# Cording.net
KiCad netlist of a schematic drawn in Altium Designer
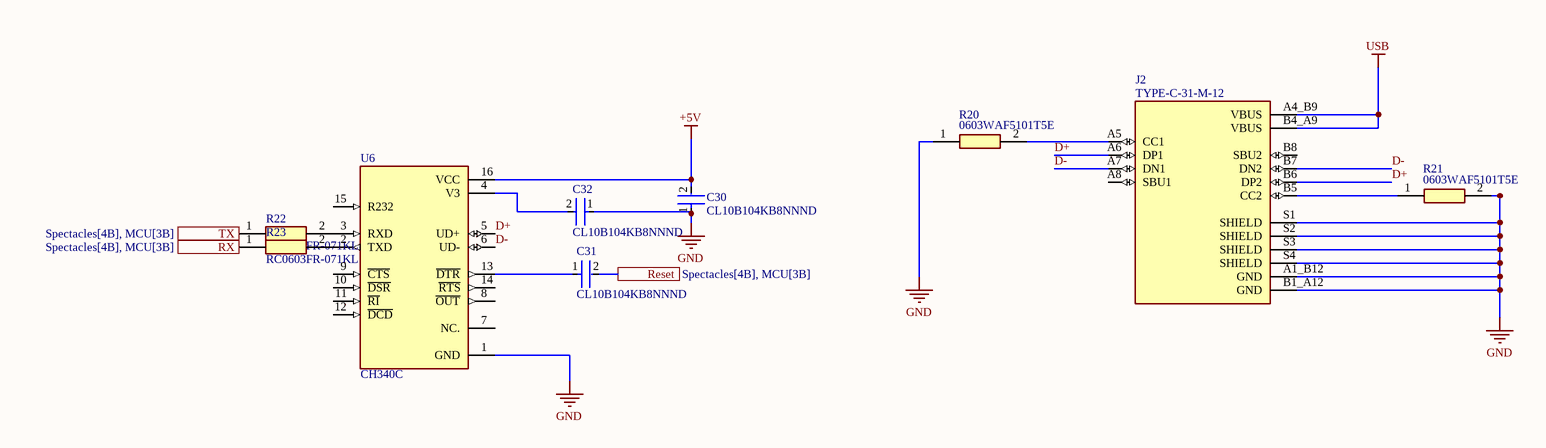
[diagram p0: Cording.SchDoc]

(export (version "E")
  (design (tool "Eeschema 10.0.6"))
  (components
    (comp (ref "C30")
      (value "CL10B104KB8NNND")
      (footprint "FP-CL10-IPC_A")
      (description "Cap Ceramic 100nF 50V X7R ±10% Pad SMD 0603 +125°C T/R")
      (fields (field (name "VOLTAGE") "50V") (field (name "TOLERANCE") "10%"))
      (libsource (lib "Altium Content Vault") (part "b4654b650e69147ec39a6b967a45e02"))
    )
    (comp (ref "C31")
      (value "CL10B104KB8NNND")
      (footprint "FP-CL10-IPC_A")
      (description "Cap Ceramic 100nF 50V X7R ±10% Pad SMD 0603 +125°C T/R")
      (fields (field (name "VOLTAGE") "50V") (field (name "TOLERANCE") "10%"))
      (libsource (lib "Altium Content Vault") (part "b4654b650e69147ec39a6b967a45e02"))
    )
    (comp (ref "C32")
      (value "CL10B104KB8NNND")
      (footprint "FP-CL10-IPC_A")
      (description "Cap Ceramic 100nF 50V X7R ±10% Pad SMD 0603 +125°C T/R")
      (fields (field (name "VOLTAGE") "50V") (field (name "TOLERANCE") "10%"))
      (libsource (lib "Altium Content Vault") (part "b4654b650e69147ec39a6b967a45e02"))
    )
    (comp (ref "J2")
      (value "TYPE-C-31-M-12")
      (footprint "HRO_TYPE-C-31-M-12")
      (description "USB Connectors 24 Receptacle 1 8.94*7.3mm RoHS")
      (fields (field (name "MF") "HRO Electronics Co., Ltd."))
      (libsource (lib "TYPE-C-31-M-12") (part "TYPE-C-31-M-12"))
    )
    (comp (ref "R20")
      (value "0603WAF5101T5E")
      (footprint "SamacSys:RESC1608X55N")
      (description "Resistor")
      (libsource (lib "*") (part "0603WAF5101T5E"))
    )
    (comp (ref "R21")
      (value "0603WAF5101T5E")
      (footprint "SamacSys:RESC1608X55N")
      (description "Resistor")
      (libsource (lib "*") (part "0603WAF5101T5E"))
    )
    (comp (ref "R22")
      (value "RC0603FR-071KL")
      (footprint "SamacSys:RESC1608X55N")
      (description "Resistor")
      (fields (field (name "MOUSER PART NUMBER") "603-RC0603FR-071KL"))
      (libsource (lib "*") (part "RC0603FR-071KL"))
    )
    (comp (ref "R23")
      (value "RC0603FR-071KL")
      (footprint "SamacSys:RESC1608X55N")
      (description "Resistor")
      (fields (field (name "MOUSER PART NUMBER") "603-RC0603FR-071KL"))
      (libsource (lib "*") (part "RC0603FR-071KL"))
    )
    (comp (ref "U6")
      (value "CH340C")
      (footprint "SOIC127P600X180-16N")
      (description "USB to serial chip CH340")
      (fields (field (name "MF") "WCH"))
      (libsource (lib "CH340C") (part "CH340C"))
    )
  )
  (nets
    (net (code "1") (name "+5V") (class "Default")
      (node (ref "C30") (pin "2") (pinfunction "2_2") (pintype "passive"))
      (node (ref "U6") (pin "16") (pinfunction "VCC_16") (pintype "power_in"))
    )
    (net (code "2") (name "/D+") (class "Default")
      (node (ref "J2") (pin "A6") (pinfunction "DP1_A6") (pintype "bidirectional"))
      (node (ref "J2") (pin "B6") (pinfunction "DP2_B6") (pintype "bidirectional"))
      (node (ref "U6") (pin "5") (pinfunction "UD+_5") (pintype "bidirectional"))
    )
    (net (code "3") (name "/D-") (class "Default")
      (node (ref "J2") (pin "A7") (pinfunction "DN1_A7") (pintype "bidirectional"))
      (node (ref "J2") (pin "B7") (pinfunction "DN2_B7") (pintype "bidirectional"))
      (node (ref "U6") (pin "6") (pinfunction "UD-_6") (pintype "bidirectional"))
    )
    (net (code "4") (name "/RX") (class "Default")
      (node (ref "R23") (pin "1") (pinfunction "1_1") (pintype "passive"))
    )
    (net (code "5") (name "/Reset") (class "Default")
      (node (ref "C31") (pin "2") (pinfunction "2_2") (pintype "passive"))
    )
    (net (code "6") (name "/TX") (class "Default")
      (node (ref "R22") (pin "1") (pinfunction "1_1") (pintype "passive"))
    )
    (net (code "7") (name "GND") (class "Default")
      (node (ref "C30") (pin "1") (pinfunction "1_1") (pintype "passive"))
      (node (ref "C32") (pin "1") (pinfunction "1_1") (pintype "passive"))
      (node (ref "J2") (pin "A1_B12") (pinfunction "GND_A1_B12") (pintype "power_in"))
      (node (ref "J2") (pin "B1_A12") (pinfunction "GND_B1_A12") (pintype "power_in"))
      (node (ref "J2") (pin "S1") (pinfunction "SHIELD_S1") (pintype "passive"))
      (node (ref "J2") (pin "S2") (pinfunction "SHIELD_S2") (pintype "passive"))
      (node (ref "J2") (pin "S3") (pinfunction "SHIELD_S3") (pintype "passive"))
      (node (ref "J2") (pin "S4") (pinfunction "SHIELD_S4") (pintype "passive"))
      (node (ref "R20") (pin "1") (pinfunction "1_1") (pintype "passive"))
      (node (ref "R21") (pin "2") (pinfunction "2_2") (pintype "passive"))
      (node (ref "U6") (pin "1") (pinfunction "GND_1") (pintype "power_in"))
    )
    (net (code "8") (name "Net-(J2-CC1)") (class "Default")
      (node (ref "J2") (pin "A5") (pinfunction "CC1_A5") (pintype "bidirectional"))
      (node (ref "R20") (pin "2") (pinfunction "2_2") (pintype "passive"))
    )
    (net (code "9") (name "Net-(J2-CC2)") (class "Default")
      (node (ref "J2") (pin "B5") (pinfunction "CC2_B5") (pintype "bidirectional"))
      (node (ref "R21") (pin "1") (pinfunction "1_1") (pintype "passive"))
    )
    (net (code "10") (name "Net-(U6-RXD)") (class "Default")
      (node (ref "R22") (pin "2") (pinfunction "2_2") (pintype "passive"))
      (node (ref "U6") (pin "3") (pinfunction "RXD_3") (pintype "input"))
    )
    (net (code "11") (name "Net-(U6-TXD)") (class "Default")
      (node (ref "R23") (pin "2") (pinfunction "2_2") (pintype "passive"))
      (node (ref "U6") (pin "2") (pinfunction "TXD_2") (pintype "output"))
    )
    (net (code "12") (name "Net-(U6-V3)") (class "Default")
      (node (ref "C32") (pin "2") (pinfunction "2_2") (pintype "passive"))
      (node (ref "U6") (pin "4") (pinfunction "V3_4") (pintype "power_in"))
    )
    (net (code "13") (name "Net-(U6-~{DTR})") (class "Default")
      (node (ref "C31") (pin "1") (pinfunction "1_1") (pintype "passive"))
      (node (ref "U6") (pin "13") (pinfunction "~{DTR}_13") (pintype "output"))
    )
    (net (code "14") (name "USB") (class "Default")
      (node (ref "J2") (pin "A4_B9") (pinfunction "VBUS_A4_B9") (pintype "power_in"))
      (node (ref "J2") (pin "B4_A9") (pinfunction "VBUS_B4_A9") (pintype "power_in"))
    )
    (net (code "15") (name "unconnected-(J2-SBU1-PadA8)") (class "Default")
      (node (ref "J2") (pin "A8") (pinfunction "SBU1_A8") (pintype "bidirectional"))
    )
    (net (code "16") (name "unconnected-(J2-SBU2-PadB8)") (class "Default")
      (node (ref "J2") (pin "B8") (pinfunction "SBU2_B8") (pintype "bidirectional"))
    )
    (net (code "17") (name "unconnected-(U6-NC.-Pad7)") (class "Default")
      (node (ref "U6") (pin "7") (pinfunction "NC._7") (pintype "passive"))
    )
    (net (code "18") (name "unconnected-(U6-R232-Pad15)") (class "Default")
      (node (ref "U6") (pin "15") (pinfunction "R232_15") (pintype "input"))
    )
    (net (code "19") (name "unconnected-(U6-~{CTS}-Pad9)") (class "Default")
      (node (ref "U6") (pin "9") (pinfunction "~{CTS}_9") (pintype "input"))
    )
    (net (code "20") (name "unconnected-(U6-~{DCD}-Pad12)") (class "Default")
      (node (ref "U6") (pin "12") (pinfunction "~{DCD}_12") (pintype "input"))
    )
    (net (code "21") (name "unconnected-(U6-~{DSR}-Pad10)") (class "Default")
      (node (ref "U6") (pin "10") (pinfunction "~{DSR}_10") (pintype "input"))
    )
    (net (code "22") (name "unconnected-(U6-~{OUT}-Pad8)") (class "Default")
      (node (ref "U6") (pin "8") (pinfunction "~{OUT}_8") (pintype "output"))
    )
    (net (code "23") (name "unconnected-(U6-~{RI}-Pad11)") (class "Default")
      (node (ref "U6") (pin "11") (pinfunction "~{RI}_11") (pintype "input"))
    )
    (net (code "24") (name "unconnected-(U6-~{RTS}-Pad14)") (class "Default")
      (node (ref "U6") (pin "14") (pinfunction "~{RTS}_14") (pintype "output"))
    )
  )
)
